# Circuito_impresion.net
KiCad netlist of a schematic drawn in EasyEDA
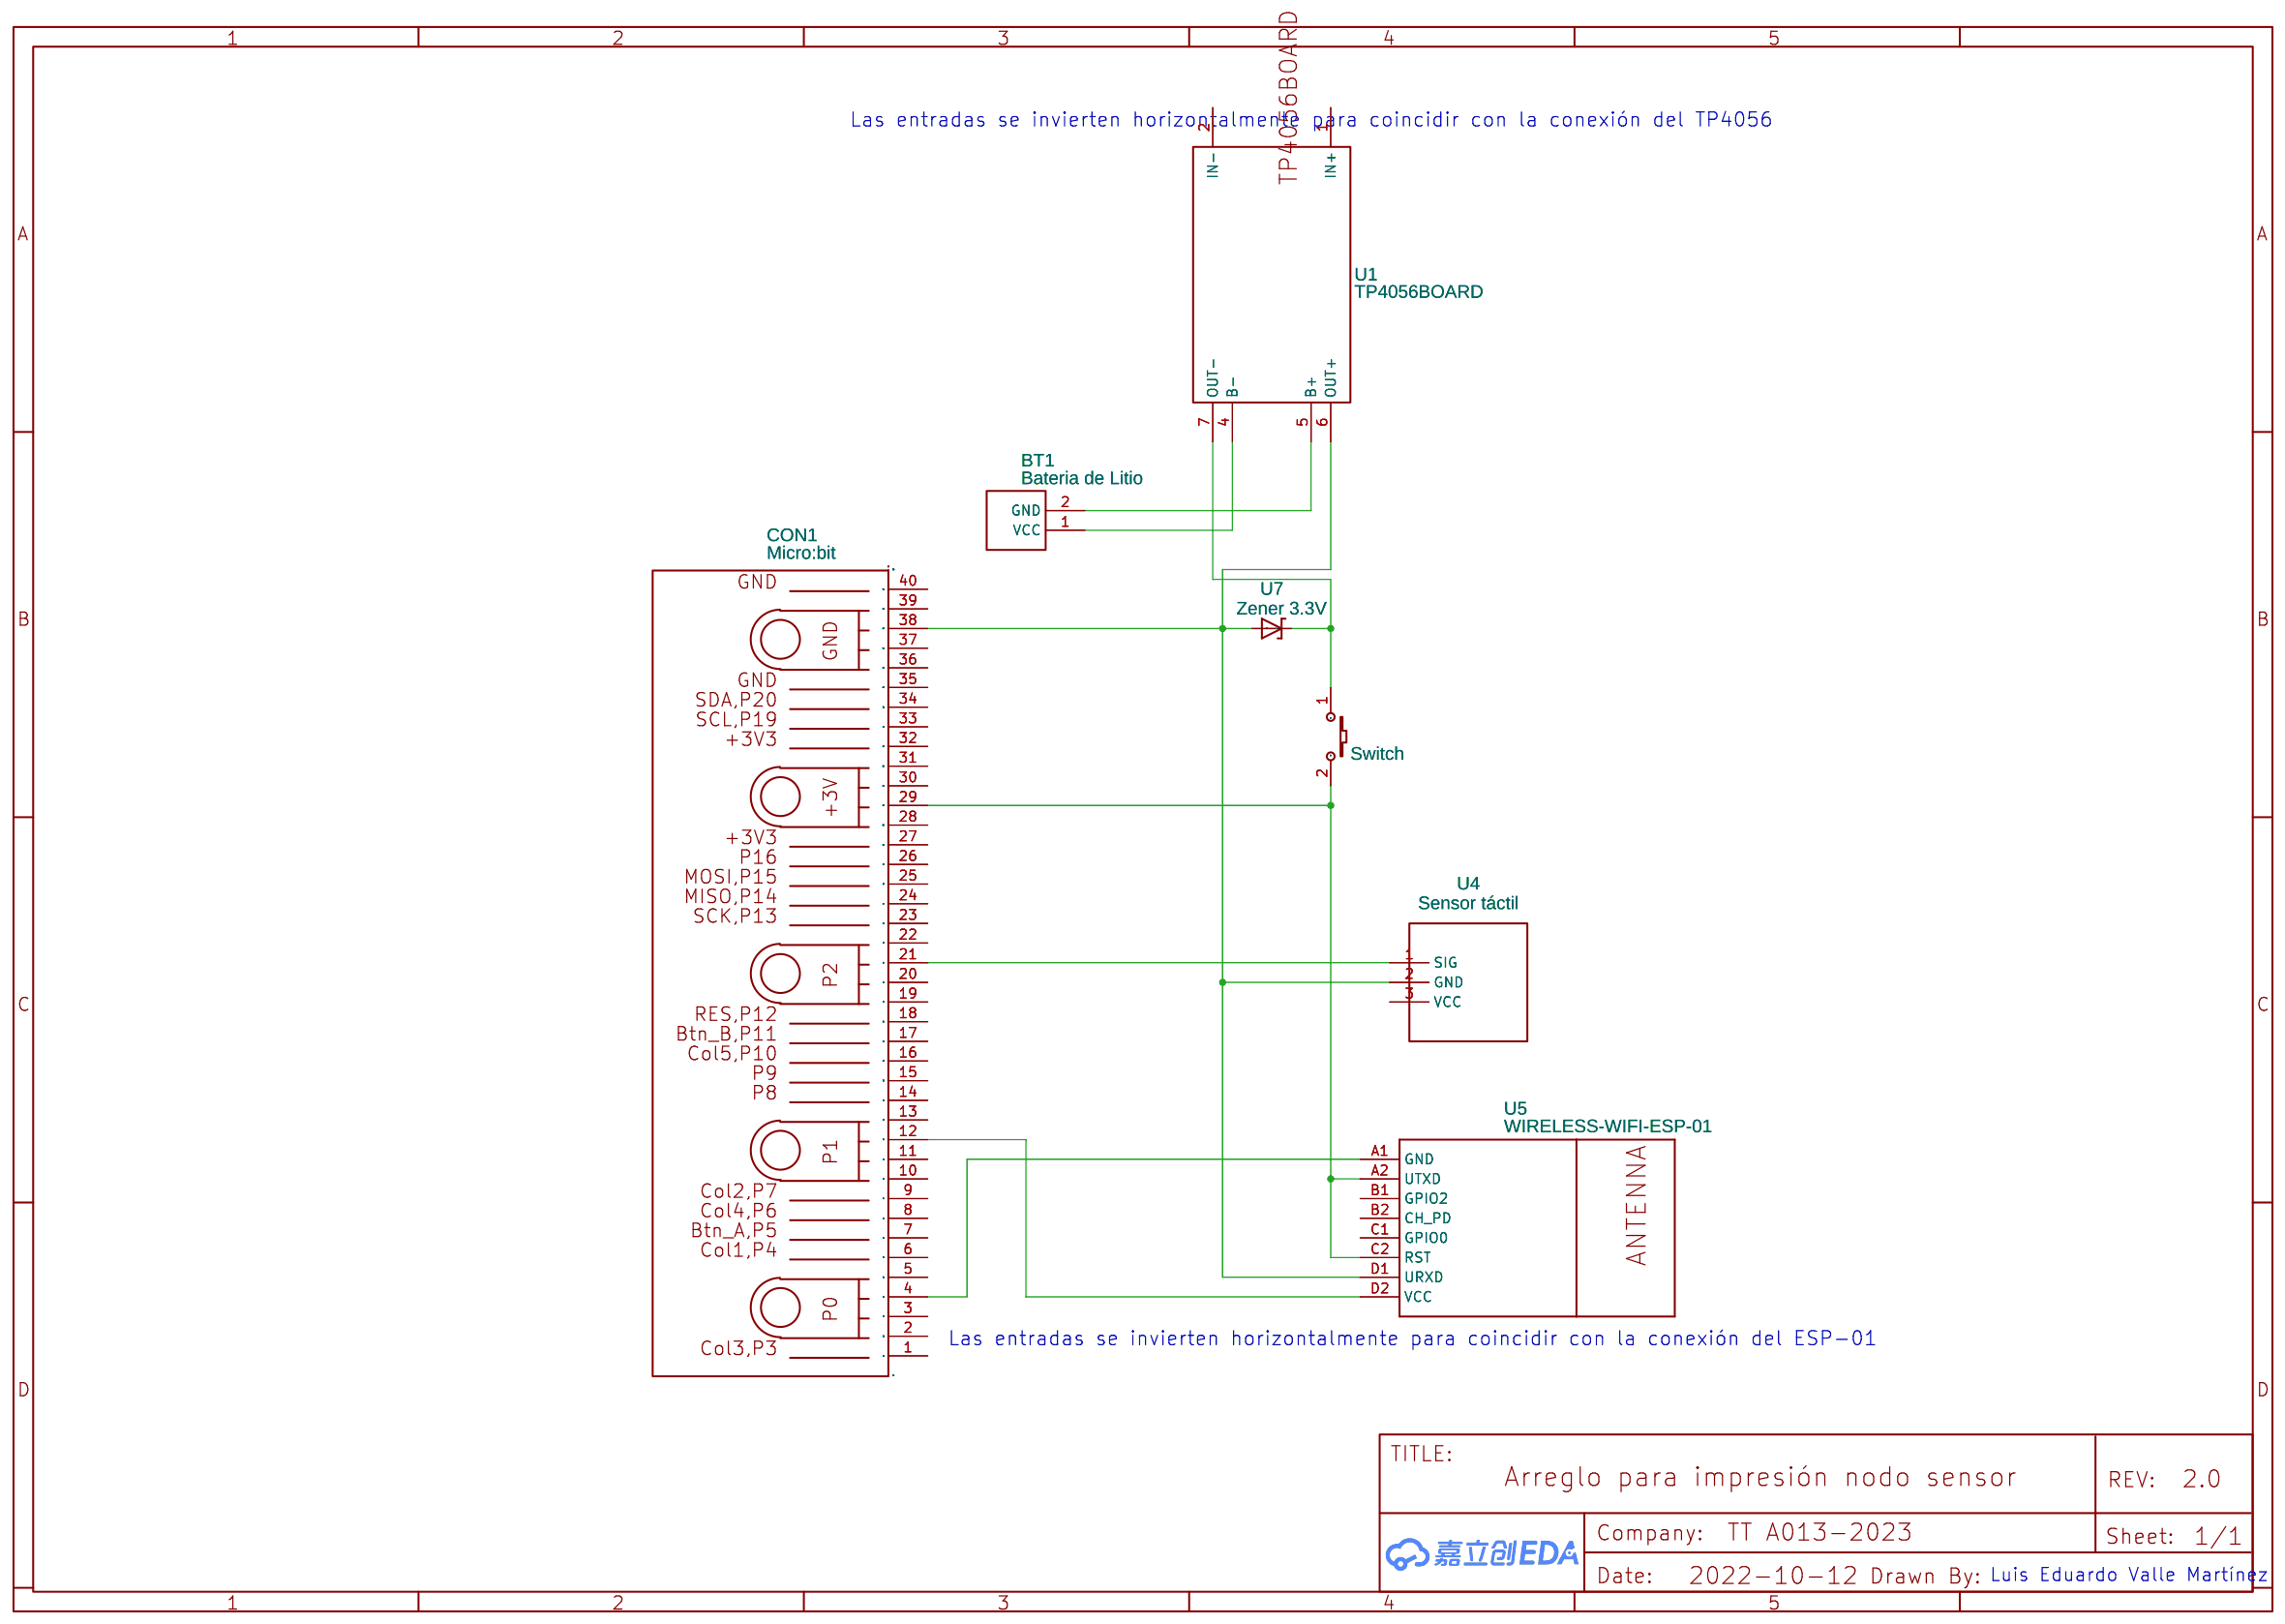
[diagram p0: schematic sheet]

(export (version "E")
  (design (tool "Eeschema 10.0.6"))
  (components
    (comp (ref "BT1")
      (value "Bateria de Litio")
      (fields
        (field (name "BOM_Manufacturer Part") "No.52Section side by side battery box")
        (field (name "BOM_Supplier Part") "C5404")
      )
      (libsource (lib "") (part "No.52Section side by side battery box"))
    )
    (comp (ref "CON1")
      (value "Micro:bit")
      (libsource (lib "") (part "CYLCONN-MICROBIT-V2-EDGE-40P-180DEG_1"))
    )
    (comp (ref "KEY1")
      (value "Switch")
      (fields
        (field (name "BOM_Manufacturer Part") "K2-1107ST-A4SW-06")
        (field (name "BOM_Supplier Part") "C118141")
      )
      (libsource (lib "") (part "K2-3.6×6.1_SMD"))
    )
    (comp (ref "U1") (value "TP4056BOARD") (libsource (lib "") (part "TP4056BOARD")))
    (comp (ref "U4")
      (value "Sensor táctil")
      (libsource (lib "") (part "TTP223B Capacitive Digital Touch Sensor Touch Button Module"))
    )
    (comp (ref "U5") (value "WIRELESS-WIFI-ESP-01") (libsource (lib "") (part "WIRELESS-WIFI-ESP-01")))
    (comp (ref "U7") (value "Zener 3.3V") (libsource (lib "") (part "DIODE-ZENER")))
  )
  (nets
    (net (code "1") (name "Net-(BT1-GND)") (class "Default")
      (node (ref "BT1") (pin "2") (pinfunction "GND_2") (pintype "unspecified"))
      (node (ref "U1") (pin "5") (pinfunction "B+_5") (pintype "unspecified"))
    )
    (net (code "2") (name "Net-(BT1-VCC)") (class "Default")
      (node (ref "BT1") (pin "1") (pinfunction "VCC_1") (pintype "unspecified"))
      (node (ref "U1") (pin "4") (pinfunction "B-_4") (pintype "unspecified"))
    )
    (net (code "3") (name "Net-(U1-OUT+)") (class "Default")
      (node (ref "CON1") (pin "38") (pinfunction "GND_38") (pintype "unspecified"))
      (node (ref "U1") (pin "6") (pinfunction "OUT+_6") (pintype "unspecified"))
      (node (ref "U4") (pin "2") (pinfunction "GND_2") (pintype "unspecified"))
      (node (ref "U5") (pin "D1") (pinfunction "URXD_D1") (pintype "unspecified"))
      (node (ref "U7") (pin "P$2") (pinfunction "A_P$2") (pintype "unspecified"))
    )
    (net (code "4") (name "Net-(U1-OUT-)") (class "Default")
      (node (ref "KEY1") (pin "1") (pinfunction "1_1") (pintype "unspecified"))
      (node (ref "U1") (pin "7") (pinfunction "OUT-_7") (pintype "unspecified"))
      (node (ref "U7") (pin "P$1") (pinfunction "C_P$1") (pintype "unspecified"))
    )
    (net (code "5") (name "Net-(U4-SIG)") (class "Default")
      (node (ref "CON1") (pin "21") (pinfunction "P2_21") (pintype "unspecified"))
      (node (ref "U4") (pin "1") (pinfunction "SIG_1") (pintype "unspecified"))
    )
    (net (code "6") (name "Net-(U5-GND)") (class "Default")
      (node (ref "CON1") (pin "4") (pinfunction "P0_4") (pintype "unspecified"))
      (node (ref "U5") (pin "A1") (pinfunction "GND_A1") (pintype "passive"))
    )
    (net (code "7") (name "Net-(U5-RST)") (class "Default")
      (node (ref "CON1") (pin "29") (pinfunction "+3V3_29") (pintype "unspecified"))
      (node (ref "KEY1") (pin "2") (pinfunction "2_2") (pintype "unspecified"))
      (node (ref "U5") (pin "A2") (pinfunction "UTXD_A2") (pintype "unspecified"))
      (node (ref "U5") (pin "C2") (pinfunction "RST_C2") (pintype "unspecified"))
    )
    (net (code "8") (name "Net-(U5-VCC)") (class "Default")
      (node (ref "CON1") (pin "12") (pinfunction "P1_12") (pintype "unspecified"))
      (node (ref "U5") (pin "D2") (pinfunction "VCC_D2") (pintype "passive"))
    )
    (net (code "9") (name "unconnected-(CON1-+3V3-Pad27)") (class "Default")
      (node (ref "CON1") (pin "27") (pinfunction "+3V3_27") (pintype "unspecified"))
    )
    (net (code "10") (name "unconnected-(CON1-+3V3-Pad28)") (class "Default")
      (node (ref "CON1") (pin "28") (pinfunction "+3V3_28") (pintype "unspecified"))
    )
    (net (code "11") (name "unconnected-(CON1-+3V3-Pad30)") (class "Default")
      (node (ref "CON1") (pin "30") (pinfunction "+3V3_30") (pintype "unspecified"))
    )
    (net (code "12") (name "unconnected-(CON1-+3V3-Pad31)") (class "Default")
      (node (ref "CON1") (pin "31") (pinfunction "+3V3_31") (pintype "unspecified"))
    )
    (net (code "13") (name "unconnected-(CON1-+3V3-Pad32)") (class "Default")
      (node (ref "CON1") (pin "32") (pinfunction "+3V3_32") (pintype "unspecified"))
    )
    (net (code "14") (name "unconnected-(CON1-GND-Pad35)") (class "Default")
      (node (ref "CON1") (pin "35") (pinfunction "GND_35") (pintype "unspecified"))
    )
    (net (code "15") (name "unconnected-(CON1-GND-Pad36)") (class "Default")
      (node (ref "CON1") (pin "36") (pinfunction "GND_36") (pintype "unspecified"))
    )
    (net (code "16") (name "unconnected-(CON1-GND-Pad37)") (class "Default")
      (node (ref "CON1") (pin "37") (pinfunction "GND_37") (pintype "unspecified"))
    )
    (net (code "17") (name "unconnected-(CON1-GND-Pad39)") (class "Default")
      (node (ref "CON1") (pin "39") (pinfunction "GND_39") (pintype "unspecified"))
    )
    (net (code "18") (name "unconnected-(CON1-GND-Pad40)") (class "Default")
      (node (ref "CON1") (pin "40") (pinfunction "GND_40") (pintype "unspecified"))
    )
    (net (code "19") (name "unconnected-(CON1-NC41-Pad41)") (class "Default")
      (node (ref "CON1") (pin "41") (pinfunction "NC41_41") (pintype "unspecified"))
    )
    (net (code "20") (name "unconnected-(CON1-NC42-Pad42)") (class "Default")
      (node (ref "CON1") (pin "42") (pinfunction "NC42_42") (pintype "unspecified"))
    )
    (net (code "21") (name "unconnected-(CON1-P0-Pad2)") (class "Default")
      (node (ref "CON1") (pin "2") (pinfunction "P0_2") (pintype "unspecified"))
    )
    (net (code "22") (name "unconnected-(CON1-P0-Pad3)") (class "Default")
      (node (ref "CON1") (pin "3") (pinfunction "P0_3") (pintype "unspecified"))
    )
    (net (code "23") (name "unconnected-(CON1-P0-Pad5)") (class "Default")
      (node (ref "CON1") (pin "5") (pinfunction "P0_5") (pintype "unspecified"))
    )
    (net (code "24") (name "unconnected-(CON1-P1-Pad10)") (class "Default")
      (node (ref "CON1") (pin "10") (pinfunction "P1_10") (pintype "unspecified"))
    )
    (net (code "25") (name "unconnected-(CON1-P1-Pad11)") (class "Default")
      (node (ref "CON1") (pin "11") (pinfunction "P1_11") (pintype "unspecified"))
    )
    (net (code "26") (name "unconnected-(CON1-P1-Pad13)") (class "Default")
      (node (ref "CON1") (pin "13") (pinfunction "P1_13") (pintype "unspecified"))
    )
    (net (code "27") (name "unconnected-(CON1-P2-Pad19)") (class "Default")
      (node (ref "CON1") (pin "19") (pinfunction "P2_19") (pintype "unspecified"))
    )
    (net (code "28") (name "unconnected-(CON1-P2-Pad20)") (class "Default")
      (node (ref "CON1") (pin "20") (pinfunction "P2_20") (pintype "unspecified"))
    )
    (net (code "29") (name "unconnected-(CON1-P2-Pad22)") (class "Default")
      (node (ref "CON1") (pin "22") (pinfunction "P2_22") (pintype "unspecified"))
    )
    (net (code "30") (name "unconnected-(CON1-P3-Pad1)") (class "Default")
      (node (ref "CON1") (pin "1") (pinfunction "P3_1") (pintype "unspecified"))
    )
    (net (code "31") (name "unconnected-(CON1-P4-Pad6)") (class "Default")
      (node (ref "CON1") (pin "6") (pinfunction "P4_6") (pintype "unspecified"))
    )
    (net (code "32") (name "unconnected-(CON1-P5-Pad7)") (class "Default")
      (node (ref "CON1") (pin "7") (pinfunction "P5_7") (pintype "unspecified"))
    )
    (net (code "33") (name "unconnected-(CON1-P6-Pad8)") (class "Default")
      (node (ref "CON1") (pin "8") (pinfunction "P6_8") (pintype "unspecified"))
    )
    (net (code "34") (name "unconnected-(CON1-P7-Pad9)") (class "Default")
      (node (ref "CON1") (pin "9") (pinfunction "P7_9") (pintype "unspecified"))
    )
    (net (code "35") (name "unconnected-(CON1-P8-Pad14)") (class "Default")
      (node (ref "CON1") (pin "14") (pinfunction "P8_14") (pintype "unspecified"))
    )
    (net (code "36") (name "unconnected-(CON1-P9-Pad15)") (class "Default")
      (node (ref "CON1") (pin "15") (pinfunction "P9_15") (pintype "unspecified"))
    )
    (net (code "37") (name "unconnected-(CON1-P10-Pad16)") (class "Default")
      (node (ref "CON1") (pin "16") (pinfunction "P10_16") (pintype "unspecified"))
    )
    (net (code "38") (name "unconnected-(CON1-P11-Pad17)") (class "Default")
      (node (ref "CON1") (pin "17") (pinfunction "P11_17") (pintype "unspecified"))
    )
    (net (code "39") (name "unconnected-(CON1-P12-Pad18)") (class "Default")
      (node (ref "CON1") (pin "18") (pinfunction "P12_18") (pintype "unspecified"))
    )
    (net (code "40") (name "unconnected-(CON1-P13-Pad23)") (class "Default")
      (node (ref "CON1") (pin "23") (pinfunction "P13_23") (pintype "unspecified"))
    )
    (net (code "41") (name "unconnected-(CON1-P14-Pad24)") (class "Default")
      (node (ref "CON1") (pin "24") (pinfunction "P14_24") (pintype "unspecified"))
    )
    (net (code "42") (name "unconnected-(CON1-P15-Pad25)") (class "Default")
      (node (ref "CON1") (pin "25") (pinfunction "P15_25") (pintype "unspecified"))
    )
    (net (code "43") (name "unconnected-(CON1-P16-Pad26)") (class "Default")
      (node (ref "CON1") (pin "26") (pinfunction "P16_26") (pintype "unspecified"))
    )
    (net (code "44") (name "unconnected-(CON1-P19-Pad33)") (class "Default")
      (node (ref "CON1") (pin "33") (pinfunction "P19_33") (pintype "unspecified"))
    )
    (net (code "45") (name "unconnected-(CON1-P20-Pad34)") (class "Default")
      (node (ref "CON1") (pin "34") (pinfunction "P20_34") (pintype "unspecified"))
    )
    (net (code "46") (name "unconnected-(U1-IN+-Pad1)") (class "Default")
      (node (ref "U1") (pin "1") (pinfunction "IN+_1") (pintype "unspecified"))
    )
    (net (code "47") (name "unconnected-(U1-IN--Pad2)") (class "Default")
      (node (ref "U1") (pin "2") (pinfunction "IN-_2") (pintype "unspecified"))
    )
    (net (code "48") (name "unconnected-(U4-VCC-Pad3)") (class "Default")
      (node (ref "U4") (pin "3") (pinfunction "VCC_3") (pintype "unspecified"))
    )
    (net (code "49") (name "unconnected-(U5-CH_PD-PadB2)") (class "Default")
      (node (ref "U5") (pin "B2") (pinfunction "CH_PD_B2") (pintype "unspecified"))
    )
    (net (code "50") (name "unconnected-(U5-GPIO0-PadC1)") (class "Default")
      (node (ref "U5") (pin "C1") (pinfunction "GPIO0_C1") (pintype "unspecified"))
    )
    (net (code "51") (name "unconnected-(U5-GPIO2-PadB1)") (class "Default")
      (node (ref "U5") (pin "B1") (pinfunction "GPIO2_B1") (pintype "unspecified"))
    )
  )
)
